# stm32f405_card.net
KiCad netlist of a schematic drawn in EAGLE
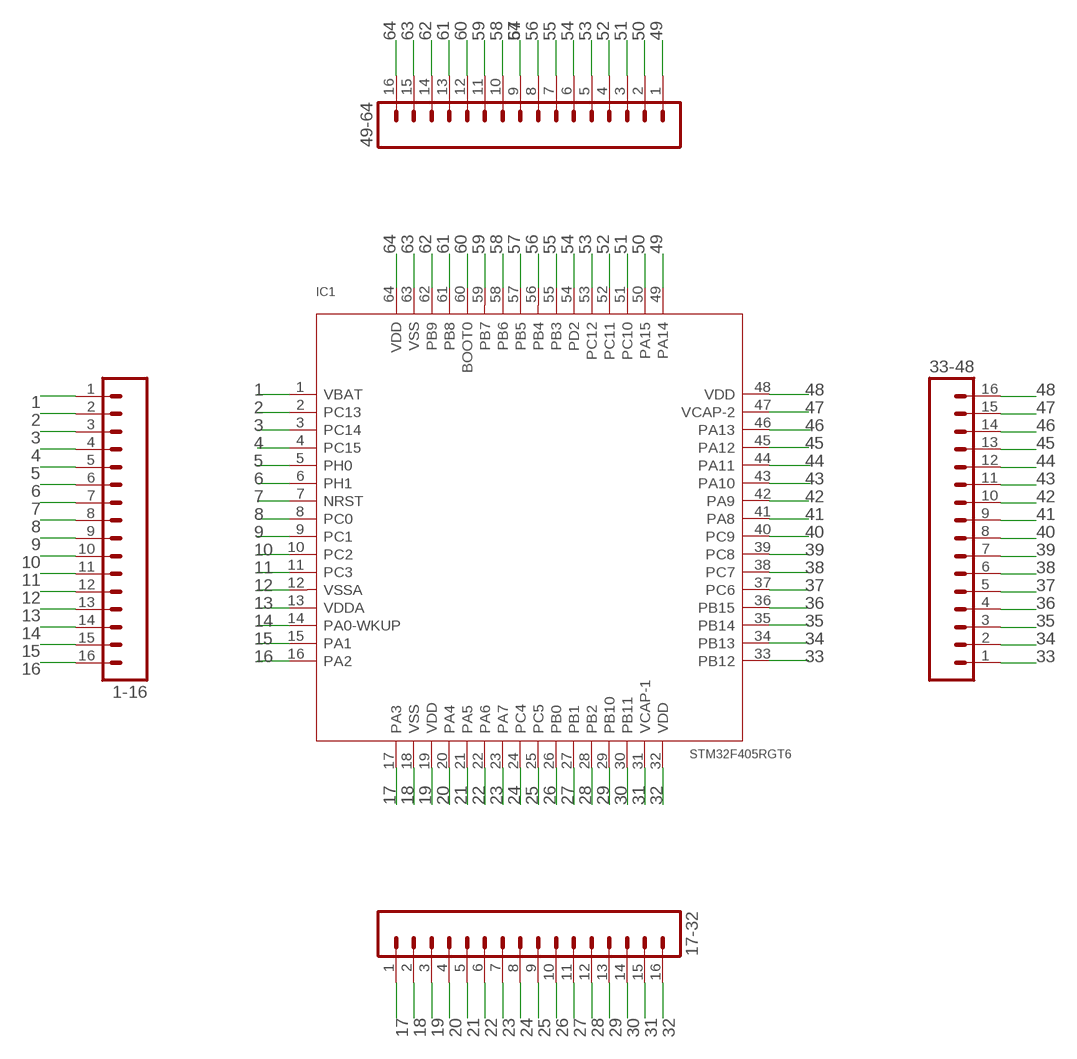
[diagram p0: schematic, sheet 1]

(export (version "E")
  (design (tool "Eeschema 10.0.6"))
  (components
    (comp (ref "1-16")
      (value "M16PTH_SQ_BOTTOM")
      (footprint "eagle-import:1X16_SQ_BOTTOM")
      (libsource (lib "eagle-import") (part "M16PTH_SQ_BOTTOM"))
    )
    (comp (ref "17-32")
      (value "M16PTH_BOTTOM")
      (footprint "eagle-import:1X16_BOTTOM")
      (libsource (lib "eagle-import") (part "M16PTH_BOTTOM"))
    )
    (comp (ref "33-48")
      (value "M16PTH_BOTTOM")
      (footprint "eagle-import:1X16_BOTTOM")
      (libsource (lib "eagle-import") (part "M16PTH_BOTTOM"))
    )
    (comp (ref "49-64")
      (value "M16PTH_BOTTOM")
      (footprint "eagle-import:1X16_BOTTOM")
      (libsource (lib "eagle-import") (part "M16PTH_BOTTOM"))
    )
    (comp (ref "IC1")
      (value "STM32F405RGT6")
      (footprint "eagle-import:LQFP64-0.5-10X10MM")
      (libsource (lib "eagle-import") (part "MCU-STM32F405RGT6(LQFP64)"))
    )
  )
  (nets
    (net (code "1") (name "/1") (class "Default")
      (node (ref "1-16") (pin "1") (pinfunction "1_1") (pintype "passive"))
      (node (ref "IC1") (pin "1") (pinfunction "VBAT_1") (pintype "bidirectional"))
    )
    (net (code "2") (name "/2") (class "Default")
      (node (ref "1-16") (pin "2") (pinfunction "2_2") (pintype "passive"))
      (node (ref "IC1") (pin "2") (pinfunction "PC13_2") (pintype "bidirectional"))
    )
    (net (code "3") (name "/3") (class "Default")
      (node (ref "1-16") (pin "3") (pinfunction "3_3") (pintype "passive"))
      (node (ref "IC1") (pin "3") (pinfunction "PC14_3") (pintype "bidirectional"))
    )
    (net (code "4") (name "/4") (class "Default")
      (node (ref "1-16") (pin "4") (pinfunction "4_4") (pintype "passive"))
      (node (ref "IC1") (pin "4") (pinfunction "PC15_4") (pintype "bidirectional"))
    )
    (net (code "5") (name "/5") (class "Default")
      (node (ref "1-16") (pin "5") (pinfunction "5_5") (pintype "passive"))
      (node (ref "IC1") (pin "5") (pinfunction "PH0_5") (pintype "bidirectional"))
    )
    (net (code "6") (name "/6") (class "Default")
      (node (ref "1-16") (pin "6") (pinfunction "6_6") (pintype "passive"))
      (node (ref "IC1") (pin "6") (pinfunction "PH1_6") (pintype "bidirectional"))
    )
    (net (code "7") (name "/7") (class "Default")
      (node (ref "1-16") (pin "7") (pinfunction "7_7") (pintype "passive"))
      (node (ref "IC1") (pin "7") (pinfunction "NRST_7") (pintype "bidirectional"))
    )
    (net (code "8") (name "/8") (class "Default")
      (node (ref "1-16") (pin "8") (pinfunction "8_8") (pintype "passive"))
      (node (ref "IC1") (pin "8") (pinfunction "PC0_8") (pintype "bidirectional"))
    )
    (net (code "9") (name "/9") (class "Default")
      (node (ref "1-16") (pin "9") (pinfunction "9_9") (pintype "passive"))
      (node (ref "IC1") (pin "9") (pinfunction "PC1_9") (pintype "bidirectional"))
    )
    (net (code "10") (name "/10") (class "Default")
      (node (ref "1-16") (pin "10") (pinfunction "10_10") (pintype "passive"))
      (node (ref "IC1") (pin "10") (pinfunction "PC2_10") (pintype "bidirectional"))
    )
    (net (code "11") (name "/11") (class "Default")
      (node (ref "1-16") (pin "11") (pinfunction "11_11") (pintype "passive"))
      (node (ref "IC1") (pin "11") (pinfunction "PC3_11") (pintype "bidirectional"))
    )
    (net (code "12") (name "/12") (class "Default")
      (node (ref "1-16") (pin "12") (pinfunction "12_12") (pintype "passive"))
      (node (ref "IC1") (pin "12") (pinfunction "VSSA_12") (pintype "bidirectional"))
    )
    (net (code "13") (name "/13") (class "Default")
      (node (ref "1-16") (pin "13") (pinfunction "13_13") (pintype "passive"))
      (node (ref "IC1") (pin "13") (pinfunction "VDDA_13") (pintype "bidirectional"))
    )
    (net (code "14") (name "/14") (class "Default")
      (node (ref "1-16") (pin "14") (pinfunction "14_14") (pintype "passive"))
      (node (ref "IC1") (pin "14") (pinfunction "PA0-WKUP_14") (pintype "bidirectional"))
    )
    (net (code "15") (name "/15") (class "Default")
      (node (ref "1-16") (pin "15") (pinfunction "15_15") (pintype "passive"))
      (node (ref "IC1") (pin "15") (pinfunction "PA1_15") (pintype "bidirectional"))
    )
    (net (code "16") (name "/16") (class "Default")
      (node (ref "1-16") (pin "16") (pinfunction "16_16") (pintype "passive"))
      (node (ref "IC1") (pin "16") (pinfunction "PA2_16") (pintype "bidirectional"))
    )
    (net (code "17") (name "/17") (class "Default")
      (node (ref "17-32") (pin "1") (pinfunction "1_1") (pintype "passive"))
      (node (ref "IC1") (pin "17") (pinfunction "PA3_17") (pintype "bidirectional"))
    )
    (net (code "18") (name "/18") (class "Default")
      (node (ref "17-32") (pin "2") (pinfunction "2_2") (pintype "passive"))
      (node (ref "IC1") (pin "18") (pinfunction "VSS_18") (pintype "bidirectional"))
    )
    (net (code "19") (name "/19") (class "Default")
      (node (ref "17-32") (pin "3") (pinfunction "3_3") (pintype "passive"))
      (node (ref "IC1") (pin "19") (pinfunction "VDD_19") (pintype "bidirectional"))
    )
    (net (code "20") (name "/20") (class "Default")
      (node (ref "17-32") (pin "4") (pinfunction "4_4") (pintype "passive"))
      (node (ref "IC1") (pin "20") (pinfunction "PA4_20") (pintype "bidirectional"))
    )
    (net (code "21") (name "/21") (class "Default")
      (node (ref "17-32") (pin "5") (pinfunction "5_5") (pintype "passive"))
      (node (ref "IC1") (pin "21") (pinfunction "PA5_21") (pintype "bidirectional"))
    )
    (net (code "22") (name "/22") (class "Default")
      (node (ref "17-32") (pin "6") (pinfunction "6_6") (pintype "passive"))
      (node (ref "IC1") (pin "22") (pinfunction "PA6_22") (pintype "bidirectional"))
    )
    (net (code "23") (name "/23") (class "Default")
      (node (ref "17-32") (pin "7") (pinfunction "7_7") (pintype "passive"))
      (node (ref "IC1") (pin "23") (pinfunction "PA7_23") (pintype "bidirectional"))
    )
    (net (code "24") (name "/24") (class "Default")
      (node (ref "17-32") (pin "8") (pinfunction "8_8") (pintype "passive"))
      (node (ref "IC1") (pin "24") (pinfunction "PC4_24") (pintype "bidirectional"))
    )
    (net (code "25") (name "/25") (class "Default")
      (node (ref "17-32") (pin "9") (pinfunction "9_9") (pintype "passive"))
      (node (ref "IC1") (pin "25") (pinfunction "PC5_25") (pintype "bidirectional"))
    )
    (net (code "26") (name "/26") (class "Default")
      (node (ref "17-32") (pin "10") (pinfunction "10_10") (pintype "passive"))
      (node (ref "IC1") (pin "26") (pinfunction "PB0_26") (pintype "bidirectional"))
    )
    (net (code "27") (name "/27") (class "Default")
      (node (ref "17-32") (pin "11") (pinfunction "11_11") (pintype "passive"))
      (node (ref "IC1") (pin "27") (pinfunction "PB1_27") (pintype "bidirectional"))
    )
    (net (code "28") (name "/28") (class "Default")
      (node (ref "17-32") (pin "12") (pinfunction "12_12") (pintype "passive"))
      (node (ref "IC1") (pin "28") (pinfunction "PB2_28") (pintype "bidirectional"))
    )
    (net (code "29") (name "/29") (class "Default")
      (node (ref "17-32") (pin "13") (pinfunction "13_13") (pintype "passive"))
      (node (ref "IC1") (pin "29") (pinfunction "PB10_29") (pintype "bidirectional"))
    )
    (net (code "30") (name "/30") (class "Default")
      (node (ref "17-32") (pin "14") (pinfunction "14_14") (pintype "passive"))
      (node (ref "IC1") (pin "30") (pinfunction "PB11_30") (pintype "bidirectional"))
    )
    (net (code "31") (name "/31") (class "Default")
      (node (ref "17-32") (pin "15") (pinfunction "15_15") (pintype "passive"))
      (node (ref "IC1") (pin "31") (pinfunction "VCAP-1_31") (pintype "bidirectional"))
    )
    (net (code "32") (name "/32") (class "Default")
      (node (ref "17-32") (pin "16") (pinfunction "16_16") (pintype "passive"))
      (node (ref "IC1") (pin "32") (pinfunction "VDD_32") (pintype "bidirectional"))
    )
    (net (code "33") (name "/33") (class "Default")
      (node (ref "33-48") (pin "1") (pinfunction "1_1") (pintype "passive"))
      (node (ref "IC1") (pin "33") (pinfunction "PB12_33") (pintype "bidirectional"))
    )
    (net (code "34") (name "/34") (class "Default")
      (node (ref "33-48") (pin "2") (pinfunction "2_2") (pintype "passive"))
      (node (ref "IC1") (pin "34") (pinfunction "PB13_34") (pintype "bidirectional"))
    )
    (net (code "35") (name "/35") (class "Default")
      (node (ref "33-48") (pin "3") (pinfunction "3_3") (pintype "passive"))
      (node (ref "IC1") (pin "35") (pinfunction "PB14_35") (pintype "bidirectional"))
    )
    (net (code "36") (name "/36") (class "Default")
      (node (ref "33-48") (pin "4") (pinfunction "4_4") (pintype "passive"))
      (node (ref "IC1") (pin "36") (pinfunction "PB15_36") (pintype "bidirectional"))
    )
    (net (code "37") (name "/37") (class "Default")
      (node (ref "33-48") (pin "5") (pinfunction "5_5") (pintype "passive"))
      (node (ref "IC1") (pin "37") (pinfunction "PC6_37") (pintype "bidirectional"))
    )
    (net (code "38") (name "/38") (class "Default")
      (node (ref "33-48") (pin "6") (pinfunction "6_6") (pintype "passive"))
      (node (ref "IC1") (pin "38") (pinfunction "PC7_38") (pintype "bidirectional"))
    )
    (net (code "39") (name "/39") (class "Default")
      (node (ref "33-48") (pin "7") (pinfunction "7_7") (pintype "passive"))
      (node (ref "IC1") (pin "39") (pinfunction "PC8_39") (pintype "bidirectional"))
    )
    (net (code "40") (name "/40") (class "Default")
      (node (ref "33-48") (pin "8") (pinfunction "8_8") (pintype "passive"))
      (node (ref "IC1") (pin "40") (pinfunction "PC9_40") (pintype "bidirectional"))
    )
    (net (code "41") (name "/41") (class "Default")
      (node (ref "33-48") (pin "9") (pinfunction "9_9") (pintype "passive"))
      (node (ref "IC1") (pin "41") (pinfunction "PA8_41") (pintype "bidirectional"))
    )
    (net (code "42") (name "/42") (class "Default")
      (node (ref "33-48") (pin "10") (pinfunction "10_10") (pintype "passive"))
      (node (ref "IC1") (pin "42") (pinfunction "PA9_42") (pintype "bidirectional"))
    )
    (net (code "43") (name "/43") (class "Default")
      (node (ref "33-48") (pin "11") (pinfunction "11_11") (pintype "passive"))
      (node (ref "IC1") (pin "43") (pinfunction "PA10_43") (pintype "bidirectional"))
    )
    (net (code "44") (name "/44") (class "Default")
      (node (ref "33-48") (pin "12") (pinfunction "12_12") (pintype "passive"))
      (node (ref "IC1") (pin "44") (pinfunction "PA11_44") (pintype "bidirectional"))
    )
    (net (code "45") (name "/45") (class "Default")
      (node (ref "33-48") (pin "13") (pinfunction "13_13") (pintype "passive"))
      (node (ref "IC1") (pin "45") (pinfunction "PA12_45") (pintype "bidirectional"))
    )
    (net (code "46") (name "/46") (class "Default")
      (node (ref "33-48") (pin "14") (pinfunction "14_14") (pintype "passive"))
      (node (ref "IC1") (pin "46") (pinfunction "PA13_46") (pintype "bidirectional"))
    )
    (net (code "47") (name "/47") (class "Default")
      (node (ref "33-48") (pin "15") (pinfunction "15_15") (pintype "passive"))
      (node (ref "IC1") (pin "47") (pinfunction "VCAP-2_47") (pintype "bidirectional"))
    )
    (net (code "48") (name "/48") (class "Default")
      (node (ref "33-48") (pin "16") (pinfunction "16_16") (pintype "passive"))
      (node (ref "IC1") (pin "48") (pinfunction "VDD_48") (pintype "bidirectional"))
    )
    (net (code "49") (name "/49") (class "Default")
      (node (ref "49-64") (pin "1") (pinfunction "1_1") (pintype "passive"))
      (node (ref "IC1") (pin "49") (pinfunction "PA14_49") (pintype "bidirectional"))
    )
    (net (code "50") (name "/50") (class "Default")
      (node (ref "49-64") (pin "2") (pinfunction "2_2") (pintype "passive"))
      (node (ref "IC1") (pin "50") (pinfunction "PA15_50") (pintype "bidirectional"))
    )
    (net (code "51") (name "/51") (class "Default")
      (node (ref "49-64") (pin "3") (pinfunction "3_3") (pintype "passive"))
      (node (ref "IC1") (pin "51") (pinfunction "PC10_51") (pintype "bidirectional"))
    )
    (net (code "52") (name "/52") (class "Default")
      (node (ref "49-64") (pin "4") (pinfunction "4_4") (pintype "passive"))
      (node (ref "IC1") (pin "52") (pinfunction "PC11_52") (pintype "bidirectional"))
    )
    (net (code "53") (name "/53") (class "Default")
      (node (ref "49-64") (pin "5") (pinfunction "5_5") (pintype "passive"))
      (node (ref "IC1") (pin "53") (pinfunction "PC12_53") (pintype "bidirectional"))
    )
    (net (code "54") (name "/54") (class "Default")
      (node (ref "49-64") (pin "6") (pinfunction "6_6") (pintype "passive"))
      (node (ref "IC1") (pin "54") (pinfunction "PD2_54") (pintype "bidirectional"))
    )
    (net (code "55") (name "/55") (class "Default")
      (node (ref "49-64") (pin "7") (pinfunction "7_7") (pintype "passive"))
      (node (ref "IC1") (pin "55") (pinfunction "PB3_55") (pintype "bidirectional"))
    )
    (net (code "56") (name "/56") (class "Default")
      (node (ref "49-64") (pin "8") (pinfunction "8_8") (pintype "passive"))
      (node (ref "IC1") (pin "56") (pinfunction "PB4_56") (pintype "bidirectional"))
    )
    (net (code "57") (name "/57") (class "Default")
      (node (ref "49-64") (pin "9") (pinfunction "9_9") (pintype "passive"))
      (node (ref "IC1") (pin "57") (pinfunction "PB5_57") (pintype "bidirectional"))
    )
    (net (code "58") (name "/58") (class "Default")
      (node (ref "49-64") (pin "10") (pinfunction "10_10") (pintype "passive"))
      (node (ref "IC1") (pin "58") (pinfunction "PB6_58") (pintype "bidirectional"))
    )
    (net (code "59") (name "/59") (class "Default")
      (node (ref "49-64") (pin "11") (pinfunction "11_11") (pintype "passive"))
      (node (ref "IC1") (pin "59") (pinfunction "PB7_59") (pintype "bidirectional"))
    )
    (net (code "60") (name "/60") (class "Default")
      (node (ref "49-64") (pin "12") (pinfunction "12_12") (pintype "passive"))
      (node (ref "IC1") (pin "60") (pinfunction "BOOT0_60") (pintype "bidirectional"))
    )
    (net (code "61") (name "/61") (class "Default")
      (node (ref "49-64") (pin "13") (pinfunction "13_13") (pintype "passive"))
      (node (ref "IC1") (pin "61") (pinfunction "PB8_61") (pintype "bidirectional"))
    )
    (net (code "62") (name "/62") (class "Default")
      (node (ref "49-64") (pin "14") (pinfunction "14_14") (pintype "passive"))
      (node (ref "IC1") (pin "62") (pinfunction "PB9_62") (pintype "bidirectional"))
    )
    (net (code "63") (name "/63") (class "Default")
      (node (ref "49-64") (pin "15") (pinfunction "15_15") (pintype "passive"))
      (node (ref "IC1") (pin "63") (pinfunction "VSS_63") (pintype "bidirectional"))
    )
    (net (code "64") (name "/64") (class "Default")
      (node (ref "49-64") (pin "16") (pinfunction "16_16") (pintype "passive"))
      (node (ref "IC1") (pin "64") (pinfunction "VDD_64") (pintype "bidirectional"))
    )
  )
)
